# Sheet1.net
KiCad netlist of a schematic drawn in Altium Designer
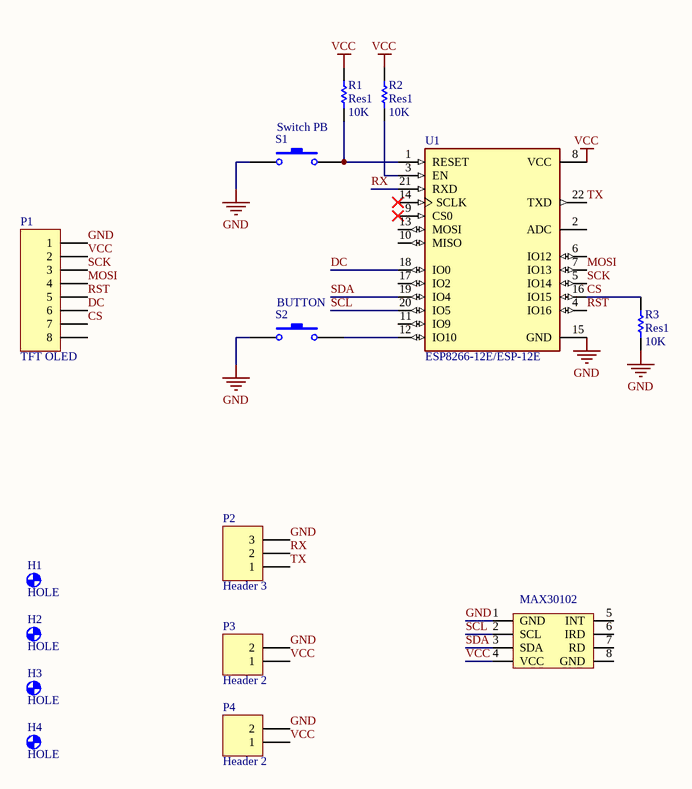
[diagram p0: Sheet1.SchDoc]

(export (version "E")
  (design (tool "Eeschema 10.0.6"))
  (components
    (comp (ref "*1")
      (value "MAX30102")
      (footprint "PCBComponent_1")
      (libsource (lib "Schlib1") (part "MAX30102"))
    )
    (comp (ref "H1")
      (value "HOLE")
      (footprint "P3.0")
      (description "MOUNTING HOLE with drill center marker")
      (libsource (lib "Mechanical And Graphical") (part "MOUNT-HOLE"))
    )
    (comp (ref "H2")
      (value "HOLE")
      (footprint "P3.0")
      (description "MOUNTING HOLE with drill center marker")
      (libsource (lib "Mechanical And Graphical") (part "MOUNT-HOLE"))
    )
    (comp (ref "H3")
      (value "HOLE")
      (footprint "P3.0")
      (description "MOUNTING HOLE with drill center marker")
      (libsource (lib "Mechanical And Graphical") (part "MOUNT-HOLE"))
    )
    (comp (ref "H4")
      (value "HOLE")
      (footprint "P3.0")
      (description "MOUNTING HOLE with drill center marker")
      (libsource (lib "Mechanical And Graphical") (part "MOUNT-HOLE"))
    )
    (comp (ref "P1")
      (value "TFT OLED")
      (footprint "HDR1X8")
      (description "Header, 8-Pin")
      (fields (field (name "PUBLISHER") "Altium Limited"))
      (libsource (lib "Miscellaneous Connectors") (part "Header 8"))
    )
    (comp (ref "P2")
      (value "Header 3")
      (footprint "HDR1X3")
      (description "Header, 3-Pin")
      (fields (field (name "PUBLISHER") "Altium Limited"))
      (libsource (lib "Miscellaneous Connectors") (part "Header 3"))
    )
    (comp (ref "P3")
      (value "Header 2")
      (footprint "HDR1X2")
      (description "Header, 2-Pin")
      (fields (field (name "PUBLISHER") "Altium Limited"))
      (libsource (lib "Miscellaneous Connectors") (part "Header 2"))
    )
    (comp (ref "P4")
      (value "Header 2")
      (footprint "HDR1X2")
      (description "Header, 2-Pin")
      (fields (field (name "PUBLISHER") "Altium Limited"))
      (libsource (lib "Miscellaneous Connectors") (part "Header 2"))
    )
    (comp (ref "R1")
      (value "Res1")
      (footprint "AXIAL-0.3")
      (description "Resistor")
      (fields (field (name "ALTIUM_VALUE") "10K") (field (name "PUBLISHER") "Altium Limited"))
      (libsource (lib "Miscellaneous Devices") (part "Res1"))
    )
    (comp (ref "R2")
      (value "Res1")
      (footprint "AXIAL-0.3")
      (description "Resistor")
      (fields (field (name "ALTIUM_VALUE") "10K") (field (name "PUBLISHER") "Altium Limited"))
      (libsource (lib "Miscellaneous Devices") (part "Res1"))
    )
    (comp (ref "R3")
      (value "Res1")
      (footprint "AXIAL-0.3")
      (description "Resistor")
      (fields (field (name "ALTIUM_VALUE") "10K") (field (name "PUBLISHER") "Altium Limited"))
      (libsource (lib "Miscellaneous Devices") (part "Res1"))
    )
    (comp (ref "S1")
      (value "Switch PB")
      (footprint "Switch - Push to On")
      (description "Push Button Switch")
      (libsource (lib "General 2") (part "Switch PB"))
    )
    (comp (ref "S2")
      (value "BUTTON")
      (footprint "Switch - Push to On")
      (description "Push Button Switch")
      (libsource (lib "General 2") (part "Switch PB"))
    )
    (comp (ref "U1")
      (value "ESP8266-12E/ESP-12E")
      (footprint "XCVR_ESP8266-12E/ESP-12E")
      (fields (field (name "MF") "AI-Thinker"))
      (libsource (lib "ESP8266-12E_ESP-12E") (part "ESP8266-12E/ESP-12E"))
    )
  )
  (nets
    (net (code "1") (name "/CS") (class "Default")
      (node (ref "P1") (pin "7") (pinfunction "7_7") (pintype "passive"))
      (node (ref "R3") (pin "1") (pinfunction "1_1") (pintype "passive"))
      (node (ref "U1") (pin "16") (pinfunction "IO15_16") (pintype "bidirectional"))
    )
    (net (code "2") (name "/DC") (class "Default")
      (node (ref "P1") (pin "6") (pinfunction "6_6") (pintype "passive"))
      (node (ref "U1") (pin "18") (pinfunction "IO0_18") (pintype "bidirectional"))
    )
    (net (code "3") (name "/MOSI") (class "Default")
      (node (ref "P1") (pin "4") (pinfunction "4_4") (pintype "passive"))
      (node (ref "U1") (pin "7") (pinfunction "IO13_7") (pintype "bidirectional"))
    )
    (net (code "4") (name "/RST") (class "Default")
      (node (ref "P1") (pin "5") (pinfunction "5_5") (pintype "passive"))
      (node (ref "U1") (pin "4") (pinfunction "IO16_4") (pintype "bidirectional"))
    )
    (net (code "5") (name "/RX") (class "Default")
      (node (ref "P2") (pin "2") (pinfunction "2_2") (pintype "passive"))
      (node (ref "U1") (pin "21") (pinfunction "RXD_21") (pintype "input"))
    )
    (net (code "6") (name "/SCK") (class "Default")
      (node (ref "P1") (pin "3") (pinfunction "3_3") (pintype "passive"))
      (node (ref "U1") (pin "5") (pinfunction "IO14_5") (pintype "bidirectional"))
    )
    (net (code "7") (name "/SCL") (class "Default")
      (node (ref "*1") (pin "2") (pinfunction "SCL_2") (pintype "passive"))
      (node (ref "U1") (pin "20") (pinfunction "IO5_20") (pintype "bidirectional"))
    )
    (net (code "8") (name "/SDA") (class "Default")
      (node (ref "*1") (pin "3") (pinfunction "SDA_3") (pintype "passive"))
      (node (ref "U1") (pin "19") (pinfunction "IO4_19") (pintype "bidirectional"))
    )
    (net (code "9") (name "/TX") (class "Default")
      (node (ref "P2") (pin "1") (pinfunction "1_1") (pintype "passive"))
      (node (ref "U1") (pin "22") (pinfunction "TXD_22") (pintype "output"))
    )
    (net (code "10") (name "GND") (class "Default")
      (node (ref "*1") (pin "1") (pinfunction "GND_1") (pintype "passive"))
      (node (ref "P1") (pin "1") (pinfunction "1_1") (pintype "passive"))
      (node (ref "P2") (pin "3") (pinfunction "3_3") (pintype "passive"))
      (node (ref "P3") (pin "2") (pinfunction "2_2") (pintype "passive"))
      (node (ref "P4") (pin "2") (pinfunction "2_2") (pintype "passive"))
      (node (ref "R3") (pin "2") (pinfunction "2_2") (pintype "passive"))
      (node (ref "S1") (pin "1") (pinfunction "1_1") (pintype "passive"))
      (node (ref "S2") (pin "1") (pinfunction "1_1") (pintype "passive"))
      (node (ref "U1") (pin "15") (pinfunction "GND_15") (pintype "power_in"))
    )
    (net (code "11") (name "Net-(U1-EN)") (class "Default")
      (node (ref "R2") (pin "2") (pinfunction "2_2") (pintype "passive"))
      (node (ref "U1") (pin "3") (pinfunction "EN_3") (pintype "input"))
    )
    (net (code "12") (name "Net-(U1-IO10)") (class "Default")
      (node (ref "S2") (pin "2") (pinfunction "2_2") (pintype "passive"))
      (node (ref "U1") (pin "12") (pinfunction "IO10_12") (pintype "bidirectional"))
    )
    (net (code "13") (name "Net-(U1-RESET)") (class "Default")
      (node (ref "R1") (pin "2") (pinfunction "2_2") (pintype "passive"))
      (node (ref "S1") (pin "2") (pinfunction "2_2") (pintype "passive"))
      (node (ref "U1") (pin "1") (pinfunction "RESET_1") (pintype "input"))
    )
    (net (code "14") (name "VCC") (class "Default")
      (node (ref "*1") (pin "4") (pinfunction "VCC_4") (pintype "passive"))
      (node (ref "P1") (pin "2") (pinfunction "2_2") (pintype "passive"))
      (node (ref "P3") (pin "1") (pinfunction "1_1") (pintype "passive"))
      (node (ref "P4") (pin "1") (pinfunction "1_1") (pintype "passive"))
      (node (ref "R1") (pin "1") (pinfunction "1_1") (pintype "passive"))
      (node (ref "R2") (pin "1") (pinfunction "1_1") (pintype "passive"))
      (node (ref "U1") (pin "8") (pinfunction "VCC_8") (pintype "power_in"))
    )
    (net (code "15") (name "unconnected-(*1C-GND-Pad8)") (class "Default")
      (node (ref "*1") (pin "8") (pinfunction "GND_8") (pintype "passive"))
    )
    (net (code "16") (name "unconnected-(*1C-INT-Pad5)") (class "Default")
      (node (ref "*1") (pin "5") (pinfunction "INT_5") (pintype "passive"))
    )
    (net (code "17") (name "unconnected-(*1C-IRD-Pad6)") (class "Default")
      (node (ref "*1") (pin "6") (pinfunction "IRD_6") (pintype "passive"))
    )
    (net (code "18") (name "unconnected-(*1C-RD-Pad7)") (class "Default")
      (node (ref "*1") (pin "7") (pinfunction "RD_7") (pintype "passive"))
    )
    (net (code "19") (name "unconnected-(P1-Pad8)") (class "Default")
      (node (ref "P1") (pin "8") (pinfunction "8_8") (pintype "passive"))
    )
    (net (code "20") (name "unconnected-(U1-ADC-Pad2)") (class "Default")
      (node (ref "U1") (pin "2") (pinfunction "ADC_2") (pintype "passive"))
    )
    (net (code "21") (name "unconnected-(U1-CS0-Pad9)") (class "Default")
      (node (ref "U1") (pin "9") (pinfunction "CS0_9") (pintype "input+no_connect"))
    )
    (net (code "22") (name "unconnected-(U1-IO2-Pad17)") (class "Default")
      (node (ref "U1") (pin "17") (pinfunction "IO2_17") (pintype "bidirectional"))
    )
    (net (code "23") (name "unconnected-(U1-IO9-Pad11)") (class "Default")
      (node (ref "U1") (pin "11") (pinfunction "IO9_11") (pintype "bidirectional"))
    )
    (net (code "24") (name "unconnected-(U1-IO12-Pad6)") (class "Default")
      (node (ref "U1") (pin "6") (pinfunction "IO12_6") (pintype "bidirectional"))
    )
    (net (code "25") (name "unconnected-(U1-MISO-Pad10)") (class "Default")
      (node (ref "U1") (pin "10") (pinfunction "MISO_10") (pintype "bidirectional"))
    )
    (net (code "26") (name "unconnected-(U1-MOSI-Pad13)") (class "Default")
      (node (ref "U1") (pin "13") (pinfunction "MOSI_13") (pintype "bidirectional"))
    )
    (net (code "27") (name "unconnected-(U1-SCLK-Pad14)") (class "Default")
      (node (ref "U1") (pin "14") (pinfunction "SCLK_14") (pintype "input+no_connect"))
    )
  )
)
